# just_a_switch-mk-1.net
KiCad netlist of a schematic drawn in EAGLE
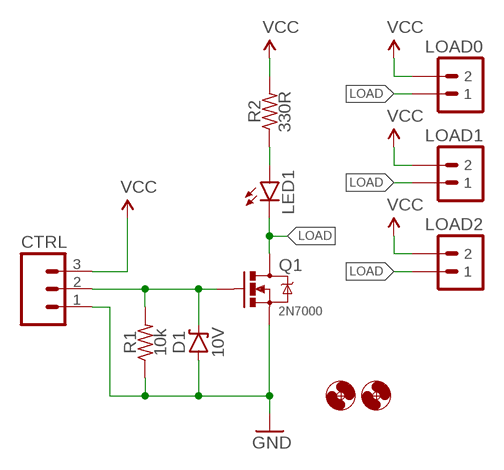
[diagram p0: schematic, sheet 1]

(export (version "E")
  (design (tool "Eeschema 10.0.6"))
  (components
    (comp (ref "CTRL")
      (value "M03PTH")
      (footprint "eagle-import:1X03")
      (libsource (lib "eagle-import") (part "M03PTH"))
    )
    (comp (ref "D1")
      (value "10V")
      (footprint "eagle-import:DIODE-7.62MM")
      (libsource (lib "eagle-import") (part "DIODE-ZENERPTH-7.62MM"))
    )
    (comp (ref "H1")
      (value "HOLE#2")
      (footprint "eagle-import:HOLE-#2")
      (libsource (lib "eagle-import") (part "HOLE#2"))
    )
    (comp (ref "H2")
      (value "HOLE#2")
      (footprint "eagle-import:HOLE-#2")
      (libsource (lib "eagle-import") (part "HOLE#2"))
    )
    (comp (ref "LED1")
      (value "LED3MM")
      (footprint "eagle-import:LED3MM")
      (libsource (lib "eagle-import") (part "LED3MM"))
    )
    (comp (ref "LOAD0")
      (value "M02PTH-2MM")
      (footprint "eagle-import:1X02-2MM-PTH")
      (libsource (lib "eagle-import") (part "M02PTH-2MM"))
    )
    (comp (ref "LOAD1")
      (value "M021X02_NO_SILK")
      (footprint "eagle-import:1X02_NO_SILK")
      (libsource (lib "eagle-import") (part "M021X02_NO_SILK"))
    )
    (comp (ref "LOAD2")
      (value "M023.5MM")
      (footprint "eagle-import:SCREWTERMINAL-3.5MM-2")
      (libsource (lib "eagle-import") (part "M023.5MM"))
    )
    (comp (ref "Q1")
      (value "2N7000")
      (footprint "eagle-import:TO-92-AMMO")
      (libsource (lib "eagle-import") (part "MOSFET-NCHANNEL2N7000-AMMO"))
    )
    (comp (ref "R1")
      (value "10k")
      (footprint "eagle-import:RESISTOR-AXIAL-PTH-7.62MM")
      (libsource (lib "eagle-import") (part "RESISTORPTH-AXIAL-7.62MM"))
    )
    (comp (ref "R2")
      (value "330R")
      (footprint "eagle-import:RESISTOR-AXIAL-PTH-7.62MM")
      (libsource (lib "eagle-import") (part "RESISTORPTH-AXIAL-7.62MM"))
    )
  )
  (nets
    (net (code "1") (name "GND") (class "Default")
      (node (ref "CTRL") (pin "1") (pinfunction "1_1") (pintype "passive"))
      (node (ref "D1") (pin "A") (pinfunction "A_A") (pintype "passive"))
      (node (ref "Q1") (pin "1") (pinfunction "S_1") (pintype "passive"))
      (node (ref "R1") (pin "P$1") (pinfunction "1_P$1") (pintype "passive"))
    )
    (net (code "2") (name "LOAD") (class "Default")
      (node (ref "LED1") (pin "K") (pinfunction "C_K") (pintype "passive"))
      (node (ref "LOAD0") (pin "P$1") (pinfunction "1_P$1") (pintype "passive"))
      (node (ref "LOAD1") (pin "1") (pinfunction "1_1") (pintype "passive"))
      (node (ref "LOAD2") (pin "1") (pinfunction "1_1") (pintype "passive"))
      (node (ref "Q1") (pin "3") (pinfunction "D_3") (pintype "passive"))
    )
    (net (code "3") (name "Net-(D1-C)") (class "Default")
      (node (ref "CTRL") (pin "2") (pinfunction "2_2") (pintype "passive"))
      (node (ref "D1") (pin "K") (pinfunction "C_K") (pintype "passive"))
      (node (ref "Q1") (pin "2") (pinfunction "G_2") (pintype "passive"))
      (node (ref "R1") (pin "P$2") (pinfunction "2_P$2") (pintype "passive"))
    )
    (net (code "4") (name "Net-(R2-1)") (class "Default")
      (node (ref "LED1") (pin "A") (pinfunction "A_A") (pintype "passive"))
      (node (ref "R2") (pin "P$1") (pinfunction "1_P$1") (pintype "passive"))
    )
    (net (code "5") (name "VCC") (class "Default")
      (node (ref "CTRL") (pin "3") (pinfunction "3_3") (pintype "passive"))
      (node (ref "LOAD0") (pin "P$2") (pinfunction "2_P$2") (pintype "passive"))
      (node (ref "LOAD1") (pin "2") (pinfunction "2_2") (pintype "passive"))
      (node (ref "LOAD2") (pin "2") (pinfunction "2_2") (pintype "passive"))
      (node (ref "R2") (pin "P$2") (pinfunction "2_P$2") (pintype "passive"))
    )
  )
)
